# schema_electrica_statie_monitorizare.net
KiCad netlist of a schematic drawn in EAGLE
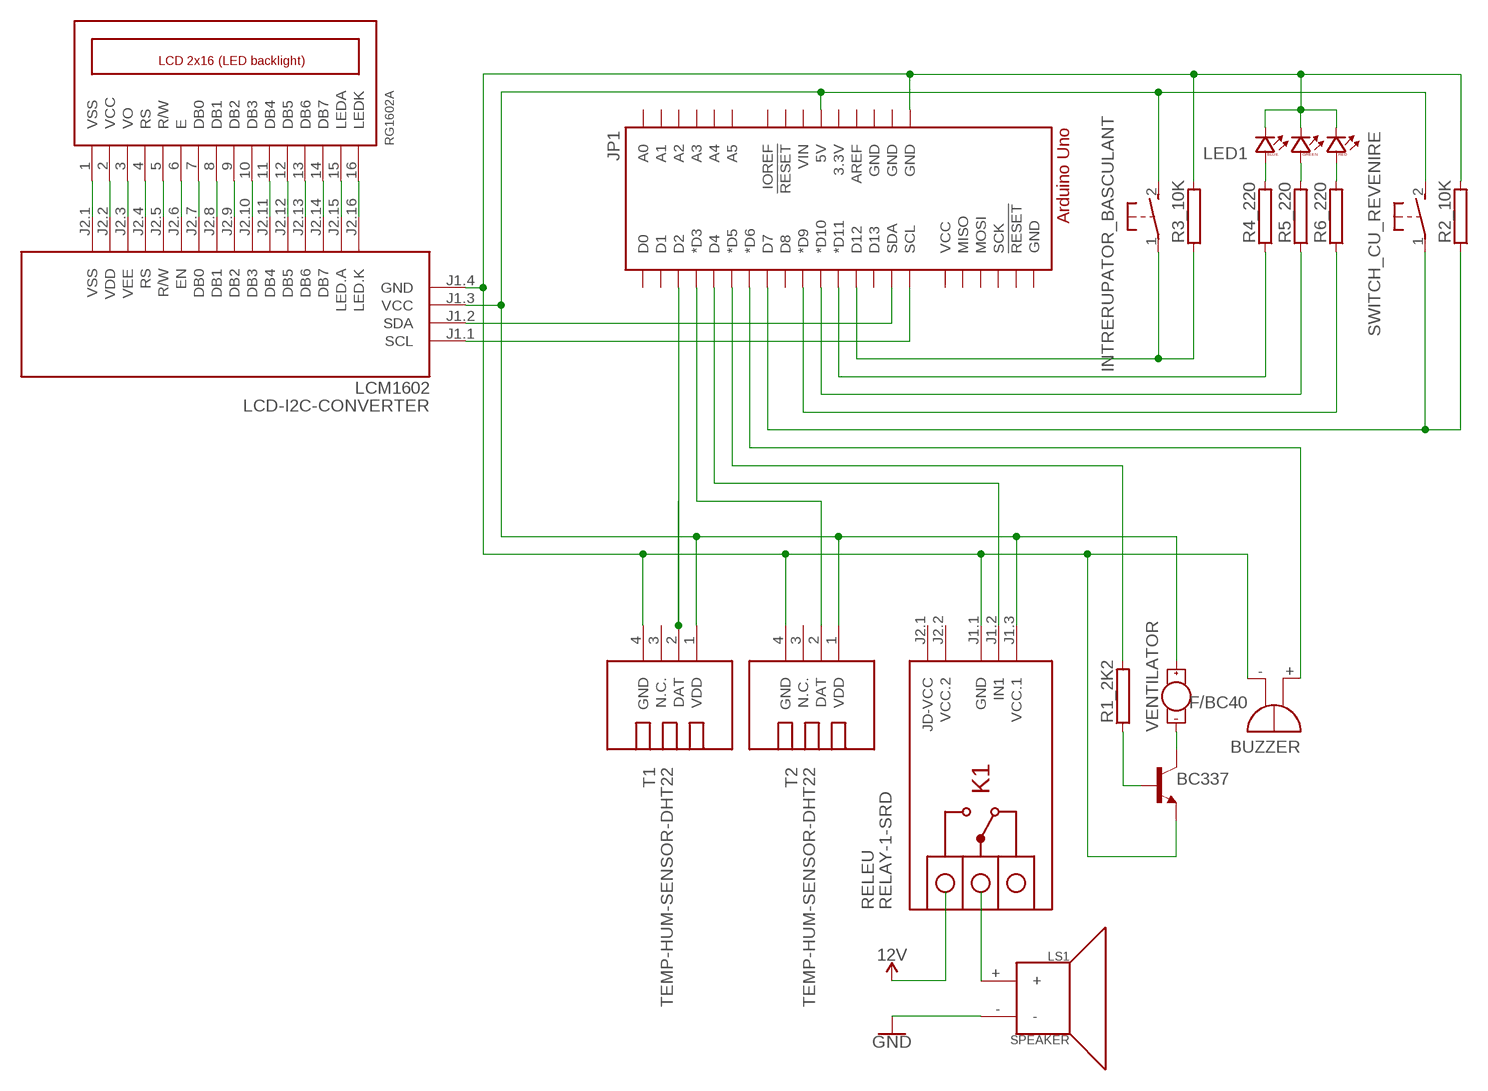
[diagram p0: schematic, sheet 1]

(export (version "E")
  (design (tool "Eeschema 10.0.6"))
  (components
    (comp (ref "BUZZER")
      (value "F/BC40")
      (footprint "eagle-import:F_BC40")
      (libsource (lib "eagle-import") (part "F/BC40"))
    )
    (comp (ref "INTRERUPATOR_BASCULANT")
      (value "31-XX")
      (footprint "eagle-import:B3F-31XX")
      (fields (field (name "MPN") "B3F-3100"))
      (libsource (lib "eagle-import") (part "31-XX"))
    )
    (comp (ref "JP1")
      (value "ARDUINO_R3")
      (footprint "eagle-import:ARDUINO_R3")
      (libsource (lib "eagle-import") (part "ARDUINO_R3"))
    )
    (comp (ref "LCM1602")
      (value "LCD-I2C-CONVERTER")
      (footprint "eagle-import:LCD-I2C-CONVERTER")
      (libsource (lib "eagle-import") (part "LCD-I2C-CONVERTER"))
    )
    (comp (ref "LED1")
      (value "F50360")
      (footprint "eagle-import:F50360")
      (libsource (lib "eagle-import") (part "F50360"))
    )
    (comp (ref "LS1")
      (value "SPEAKER")
      (footprint "eagle-import:PCB_MOUNT_SPEAKER")
      (libsource (lib "eagle-import") (part "SPEAKER"))
    )
    (comp (ref "R1_2K2")
      (value "RAC01")
      (footprint "eagle-import:AC01")
      (libsource (lib "eagle-import") (part "RAC01"))
    )
    (comp (ref "R2_10K")
      (value "RAC01")
      (footprint "eagle-import:AC01")
      (libsource (lib "eagle-import") (part "RAC01"))
    )
    (comp (ref "R3_10K")
      (value "RAC01")
      (footprint "eagle-import:AC01")
      (libsource (lib "eagle-import") (part "RAC01"))
    )
    (comp (ref "R4_220")
      (value "RAC01")
      (footprint "eagle-import:AC01")
      (libsource (lib "eagle-import") (part "RAC01"))
    )
    (comp (ref "R5_220")
      (value "RAC01")
      (footprint "eagle-import:AC01")
      (libsource (lib "eagle-import") (part "RAC01"))
    )
    (comp (ref "R6_220")
      (value "RAC01")
      (footprint "eagle-import:AC01")
      (libsource (lib "eagle-import") (part "RAC01"))
    )
    (comp (ref "RELEU")
      (value "RELAY-1-SRD")
      (footprint "eagle-import:RELAY-1-SRD")
      (libsource (lib "eagle-import") (part "RELAY-1-SRD"))
    )
    (comp (ref "RG1602A")
      (value "LCD_2X16_SIL")
      (footprint "eagle-import:HY-1602F")
      (libsource (lib "eagle-import") (part "LCD_2X16_SIL"))
    )
    (comp (ref "SWITCH_CU_REVENIRE")
      (value "31-XX")
      (footprint "eagle-import:B3F-31XX")
      (fields (field (name "MPN") "B3F-3100"))
      (libsource (lib "eagle-import") (part "31-XX"))
    )
    (comp (ref "T1")
      (value "TEMP-HUM-SENSOR-DHT22")
      (footprint "eagle-import:TEMP-HUM-SENSOR-DHT22")
      (libsource (lib "eagle-import") (part "TEMP-HUM-SENSOR-DHT22"))
    )
    (comp (ref "T2")
      (value "TEMP-HUM-SENSOR-DHT22")
      (footprint "eagle-import:TEMP-HUM-SENSOR-DHT22")
      (libsource (lib "eagle-import") (part "TEMP-HUM-SENSOR-DHT22"))
    )
    (comp (ref "T3")
      (value "BC337")
      (footprint "eagle-import:TO92")
      (libsource (lib "eagle-import") (part "BC337"))
    )
    (comp (ref "VENTILATOR")
      (value "MOTOR10MM")
      (footprint "eagle-import:VIBE-MOTOR-10MM")
      (libsource (lib "eagle-import") (part "MOTOR10MM"))
    )
  )
  (nets
    (net (code "1") (name "/VCC.2") (class "Default")
      (node (ref "RELEU") (pin "J2.2") (pinfunction "VCC.2_J2.2") (pintype "power_in"))
    )
    (net (code "3") (name "GND") (class "Default")
      (node (ref "LS1") (pin "-") (pinfunction "-_-") (pintype "bidirectional"))
    )
    (net (code "4") (name "Net-(INTRERUPATOR_BASCULANT-P)") (class "Default")
      (node (ref "INTRERUPATOR_BASCULANT") (pin "1") (pinfunction "P_1") (pintype "passive"))
      (node (ref "JP1") (pin "D12") (pinfunction "D12_D12") (pintype "bidirectional"))
      (node (ref "R3_10K") (pin "1") (pinfunction "1_1") (pintype "passive"))
    )
    (net (code "5") (name "Net-(INTRERUPATOR_BASCULANT-S)") (class "Default")
      (node (ref "INTRERUPATOR_BASCULANT") (pin "2") (pinfunction "S_2") (pintype "passive"))
      (node (ref "JP1") (pin "5V") (pinfunction "5V_5V") (pintype "bidirectional"))
      (node (ref "LCM1602") (pin "J1.3") (pinfunction "VCC_J1.3") (pintype "bidirectional"))
      (node (ref "RELEU") (pin "J1.3") (pinfunction "VCC.1_J1.3") (pintype "power_in"))
      (node (ref "SWITCH_CU_REVENIRE") (pin "2") (pinfunction "S_2") (pintype "passive"))
      (node (ref "T1") (pin "1") (pinfunction "VDD_1") (pintype "power_in"))
      (node (ref "T2") (pin "1") (pinfunction "VDD_1") (pintype "power_in"))
      (node (ref "VENTILATOR") (pin "+") (pinfunction "+_+") (pintype "bidirectional"))
    )
    (net (code "6") (name "Net-(JP1-*D3)") (class "Default")
      (node (ref "JP1") (pin "D3") (pinfunction "*D3_D3") (pintype "bidirectional"))
      (node (ref "T2") (pin "2") (pinfunction "DAT_2") (pintype "bidirectional"))
    )
    (net (code "7") (name "Net-(JP1-*D5)") (class "Default")
      (node (ref "JP1") (pin "D5") (pinfunction "*D5_D5") (pintype "bidirectional"))
      (node (ref "R1_2K2") (pin "2") (pinfunction "2_2") (pintype "passive"))
    )
    (net (code "8") (name "Net-(JP1-*D6)") (class "Default")
      (node (ref "BUZZER") (pin "+") (pinfunction "+_+") (pintype "passive"))
      (node (ref "JP1") (pin "D6") (pinfunction "*D6_D6") (pintype "bidirectional"))
    )
    (net (code "9") (name "Net-(JP1-*D9)") (class "Default")
      (node (ref "JP1") (pin "D9") (pinfunction "*D9_D9") (pintype "bidirectional"))
      (node (ref "R6_220") (pin "1") (pinfunction "1_1") (pintype "passive"))
    )
    (net (code "10") (name "Net-(JP1-*D10)") (class "Default")
      (node (ref "JP1") (pin "D10") (pinfunction "*D10_D10") (pintype "bidirectional"))
      (node (ref "R5_220") (pin "1") (pinfunction "1_1") (pintype "passive"))
    )
    (net (code "11") (name "Net-(JP1-*D11)") (class "Default")
      (node (ref "JP1") (pin "D11") (pinfunction "*D11_D11") (pintype "bidirectional"))
      (node (ref "R4_220") (pin "1") (pinfunction "1_1") (pintype "passive"))
    )
    (net (code "12") (name "Net-(LCM1602-DB0)") (class "Default")
      (node (ref "LCM1602") (pin "J2.7") (pinfunction "DB0_J2.7") (pintype "bidirectional"))
      (node (ref "RG1602A") (pin "7") (pinfunction "DB0_7") (pintype "bidirectional"))
    )
    (net (code "13") (name "Net-(LCM1602-DB1)") (class "Default")
      (node (ref "LCM1602") (pin "J2.8") (pinfunction "DB1_J2.8") (pintype "bidirectional"))
      (node (ref "RG1602A") (pin "8") (pinfunction "DB1_8") (pintype "bidirectional"))
    )
    (net (code "14") (name "Net-(LCM1602-DB2)") (class "Default")
      (node (ref "LCM1602") (pin "J2.9") (pinfunction "DB2_J2.9") (pintype "bidirectional"))
      (node (ref "RG1602A") (pin "9") (pinfunction "DB2_9") (pintype "bidirectional"))
    )
    (net (code "15") (name "Net-(LCM1602-DB3)") (class "Default")
      (node (ref "LCM1602") (pin "J2.10") (pinfunction "DB3_J2.10") (pintype "bidirectional"))
      (node (ref "RG1602A") (pin "10") (pinfunction "DB3_10") (pintype "bidirectional"))
    )
    (net (code "16") (name "Net-(LCM1602-DB4)") (class "Default")
      (node (ref "LCM1602") (pin "J2.11") (pinfunction "DB4_J2.11") (pintype "bidirectional"))
      (node (ref "RG1602A") (pin "11") (pinfunction "DB4_11") (pintype "bidirectional"))
    )
    (net (code "17") (name "Net-(LCM1602-DB5)") (class "Default")
      (node (ref "LCM1602") (pin "J2.12") (pinfunction "DB5_J2.12") (pintype "bidirectional"))
      (node (ref "RG1602A") (pin "12") (pinfunction "DB5_12") (pintype "bidirectional"))
    )
    (net (code "18") (name "Net-(LCM1602-DB6)") (class "Default")
      (node (ref "LCM1602") (pin "J2.13") (pinfunction "DB6_J2.13") (pintype "bidirectional"))
      (node (ref "RG1602A") (pin "13") (pinfunction "DB6_13") (pintype "bidirectional"))
    )
    (net (code "19") (name "Net-(LCM1602-DB7)") (class "Default")
      (node (ref "LCM1602") (pin "J2.14") (pinfunction "DB7_J2.14") (pintype "bidirectional"))
      (node (ref "RG1602A") (pin "14") (pinfunction "DB7_14") (pintype "bidirectional"))
    )
    (net (code "20") (name "Net-(LCM1602-EN)") (class "Default")
      (node (ref "LCM1602") (pin "J2.6") (pinfunction "EN_J2.6") (pintype "bidirectional"))
      (node (ref "RG1602A") (pin "6") (pinfunction "E_6") (pintype "input"))
    )
    (net (code "21") (name "Net-(LCM1602-GND)") (class "Default")
      (node (ref "BUZZER") (pin "-") (pinfunction "-_-") (pintype "passive"))
      (node (ref "JP1") (pin "GND@2") (pinfunction "GND_GND@2") (pintype "bidirectional"))
      (node (ref "LCM1602") (pin "J1.4") (pinfunction "GND_J1.4") (pintype "power_in"))
      (node (ref "LED1") (pin "BC") (pinfunction "BC_BC") (pintype "passive"))
      (node (ref "LED1") (pin "GC") (pinfunction "GC_GC") (pintype "passive"))
      (node (ref "LED1") (pin "RC") (pinfunction "RC_RC") (pintype "passive"))
      (node (ref "R2_10K") (pin "2") (pinfunction "2_2") (pintype "passive"))
      (node (ref "R3_10K") (pin "2") (pinfunction "2_2") (pintype "passive"))
      (node (ref "RELEU") (pin "J1.1") (pinfunction "GND_J1.1") (pintype "power_in"))
      (node (ref "T1") (pin "4") (pinfunction "GND_4") (pintype "power_in"))
      (node (ref "T2") (pin "4") (pinfunction "GND_4") (pintype "power_in"))
      (node (ref "T3") (pin "1") (pinfunction "E_1") (pintype "passive"))
    )
    (net (code "22") (name "Net-(LCM1602-LED.A)") (class "Default")
      (node (ref "LCM1602") (pin "J2.15") (pinfunction "LED.A_J2.15") (pintype "bidirectional"))
      (node (ref "RG1602A") (pin "15") (pinfunction "LEDA_15") (pintype "passive"))
    )
    (net (code "23") (name "Net-(LCM1602-LED.K)") (class "Default")
      (node (ref "LCM1602") (pin "J2.16") (pinfunction "LED.K_J2.16") (pintype "bidirectional"))
      (node (ref "RG1602A") (pin "16") (pinfunction "LEDK_16") (pintype "passive"))
    )
    (net (code "24") (name "Net-(LCM1602-RS)") (class "Default")
      (node (ref "LCM1602") (pin "J2.4") (pinfunction "RS_J2.4") (pintype "bidirectional"))
      (node (ref "RG1602A") (pin "4") (pinfunction "RS_4") (pintype "input"))
    )
    (net (code "25") (name "Net-(LCM1602-R{slash}W)") (class "Default")
      (node (ref "LCM1602") (pin "J2.5") (pinfunction "R/W_J2.5") (pintype "bidirectional"))
      (node (ref "RG1602A") (pin "5") (pinfunction "R/W_5") (pintype "input"))
    )
    (net (code "26") (name "Net-(LCM1602-SCL)") (class "Default")
      (node (ref "JP1") (pin "SCL") (pinfunction "SCL_SCL") (pintype "bidirectional"))
      (node (ref "LCM1602") (pin "J1.1") (pinfunction "SCL_J1.1") (pintype "power_in"))
    )
    (net (code "27") (name "Net-(LCM1602-SDA)") (class "Default")
      (node (ref "JP1") (pin "SDA") (pinfunction "SDA_SDA") (pintype "bidirectional"))
      (node (ref "LCM1602") (pin "J1.2") (pinfunction "SDA_J1.2") (pintype "bidirectional"))
    )
    (net (code "28") (name "Net-(LCM1602-VDD)") (class "Default")
      (node (ref "LCM1602") (pin "J2.2") (pinfunction "VDD_J2.2") (pintype "bidirectional"))
      (node (ref "RG1602A") (pin "2") (pinfunction "VCC_2") (pintype "power_in"))
    )
    (net (code "29") (name "Net-(LCM1602-VEE)") (class "Default")
      (node (ref "LCM1602") (pin "J2.3") (pinfunction "VEE_J2.3") (pintype "bidirectional"))
      (node (ref "RG1602A") (pin "3") (pinfunction "VO_3") (pintype "input"))
    )
    (net (code "30") (name "Net-(LCM1602-VSS)") (class "Default")
      (node (ref "LCM1602") (pin "J2.1") (pinfunction "VSS_J2.1") (pintype "bidirectional"))
      (node (ref "RG1602A") (pin "1") (pinfunction "VSS_1") (pintype "power_in"))
    )
    (net (code "31") (name "Net-(LED1-PadBA)") (class "Default")
      (node (ref "LED1") (pin "BA") (pinfunction "BA_BA") (pintype "passive"))
      (node (ref "R4_220") (pin "2") (pinfunction "2_2") (pintype "passive"))
    )
    (net (code "32") (name "Net-(LED1-PadGA)") (class "Default")
      (node (ref "LED1") (pin "GA") (pinfunction "GA_GA") (pintype "passive"))
      (node (ref "R5_220") (pin "2") (pinfunction "2_2") (pintype "passive"))
    )
    (net (code "33") (name "Net-(LED1-PadRA)") (class "Default")
      (node (ref "LED1") (pin "RA") (pinfunction "RA_RA") (pintype "passive"))
      (node (ref "R6_220") (pin "2") (pinfunction "2_2") (pintype "passive"))
    )
    (net (code "34") (name "Net-(RELEU-IN1)") (class "Default")
      (node (ref "JP1") (pin "D4") (pinfunction "D4_D4") (pintype "bidirectional"))
      (node (ref "RELEU") (pin "J1.2") (pinfunction "IN1_J1.2") (pintype "bidirectional"))
    )
    (net (code "35") (name "Net-(SWITCH_CU_REVENIRE-P)") (class "Default")
      (node (ref "JP1") (pin "D7") (pinfunction "D7_D7") (pintype "bidirectional"))
      (node (ref "R2_10K") (pin "1") (pinfunction "1_1") (pintype "passive"))
      (node (ref "SWITCH_CU_REVENIRE") (pin "1") (pinfunction "P_1") (pintype "passive"))
    )
    (net (code "36") (name "Net-(T1-DAT)") (class "Default")
      (node (ref "JP1") (pin "D2") (pinfunction "D2_D2") (pintype "bidirectional"))
      (node (ref "T1") (pin "2") (pinfunction "DAT_2") (pintype "bidirectional"))
    )
    (net (code "37") (name "Net-(T3-B)") (class "Default")
      (node (ref "R1_2K2") (pin "1") (pinfunction "1_1") (pintype "passive"))
      (node (ref "T3") (pin "2") (pinfunction "B_2") (pintype "passive"))
    )
    (net (code "38") (name "Net-(T3-C)") (class "Default")
      (node (ref "T3") (pin "3") (pinfunction "C_3") (pintype "passive"))
      (node (ref "VENTILATOR") (pin "-") (pinfunction "-_-") (pintype "bidirectional"))
    )
    (net (code "39") (name "unconnected-(JP1-GND-PadGND@1)") (class "Default")
      (node (ref "JP1") (pin "GND@1") (pinfunction "GND_GND@1") (pintype "bidirectional"))
    )
    (net (code "40") (name "unconnected-(JP1-GND-PadGND@3)") (class "Default")
      (node (ref "JP1") (pin "GND@3") (pinfunction "GND_GND@3") (pintype "bidirectional"))
    )
    (net (code "41") (name "unconnected-(JP1-GND-PadGND@4)") (class "Default")
      (node (ref "JP1") (pin "GND@4") (pinfunction "GND_GND@4") (pintype "bidirectional"))
    )
    (net (code "42") (name "unconnected-(JP1-Pad3.3V)") (class "Default")
      (node (ref "JP1") (pin "3.3V") (pinfunction "3.3V_3.3V") (pintype "bidirectional"))
    )
    (net (code "43") (name "unconnected-(JP1-PadA0)") (class "Default")
      (node (ref "JP1") (pin "A0") (pinfunction "A0_A0") (pintype "bidirectional"))
    )
    (net (code "44") (name "unconnected-(JP1-PadA1)") (class "Default")
      (node (ref "JP1") (pin "A1") (pinfunction "A1_A1") (pintype "bidirectional"))
    )
    (net (code "45") (name "unconnected-(JP1-PadA2)") (class "Default")
      (node (ref "JP1") (pin "A2") (pinfunction "A2_A2") (pintype "bidirectional"))
    )
    (net (code "46") (name "unconnected-(JP1-PadA3)") (class "Default")
      (node (ref "JP1") (pin "A3") (pinfunction "A3_A3") (pintype "bidirectional"))
    )
    (net (code "47") (name "unconnected-(JP1-PadA4)") (class "Default")
      (node (ref "JP1") (pin "A4") (pinfunction "A4_A4") (pintype "bidirectional"))
    )
    (net (code "48") (name "unconnected-(JP1-PadA5)") (class "Default")
      (node (ref "JP1") (pin "A5") (pinfunction "A5_A5") (pintype "bidirectional"))
    )
    (net (code "49") (name "unconnected-(JP1-PadAREF)") (class "Default")
      (node (ref "JP1") (pin "AREF") (pinfunction "AREF_AREF") (pintype "bidirectional"))
    )
    (net (code "50") (name "unconnected-(JP1-PadD0)") (class "Default")
      (node (ref "JP1") (pin "D0") (pinfunction "D0_D0") (pintype "bidirectional"))
    )
    (net (code "51") (name "unconnected-(JP1-PadD1)") (class "Default")
      (node (ref "JP1") (pin "D1") (pinfunction "D1_D1") (pintype "bidirectional"))
    )
    (net (code "52") (name "unconnected-(JP1-PadD8)") (class "Default")
      (node (ref "JP1") (pin "D8") (pinfunction "D8_D8") (pintype "bidirectional"))
    )
    (net (code "53") (name "unconnected-(JP1-PadD13)") (class "Default")
      (node (ref "JP1") (pin "D13") (pinfunction "D13_D13") (pintype "bidirectional"))
    )
    (net (code "54") (name "unconnected-(JP1-PadIOREF)") (class "Default")
      (node (ref "JP1") (pin "IOREF") (pinfunction "IOREF_IOREF") (pintype "bidirectional"))
    )
    (net (code "55") (name "unconnected-(JP1-PadMISO)") (class "Default")
      (node (ref "JP1") (pin "MISO") (pinfunction "MISO_MISO") (pintype "bidirectional"))
    )
    (net (code "56") (name "unconnected-(JP1-PadMOSI)") (class "Default")
      (node (ref "JP1") (pin "MOSI") (pinfunction "MOSI_MOSI") (pintype "bidirectional"))
    )
    (net (code "57") (name "unconnected-(JP1-PadSCK)") (class "Default")
      (node (ref "JP1") (pin "SCK") (pinfunction "SCK_SCK") (pintype "bidirectional"))
    )
    (net (code "58") (name "unconnected-(JP1-PadVCC)") (class "Default")
      (node (ref "JP1") (pin "VCC") (pinfunction "VCC_VCC") (pintype "bidirectional"))
    )
    (net (code "59") (name "unconnected-(JP1-PadVIN)") (class "Default")
      (node (ref "JP1") (pin "VIN") (pinfunction "VIN_VIN") (pintype "bidirectional"))
    )
    (net (code "60") (name "unconnected-(JP1-~{RESET}-PadRESET@1)") (class "Default")
      (node (ref "JP1") (pin "RESET@1") (pinfunction "~{RESET}_RESET@1") (pintype "bidirectional"))
    )
    (net (code "61") (name "unconnected-(JP1-~{RESET}-PadRESET@2)") (class "Default")
      (node (ref "JP1") (pin "RESET@2") (pinfunction "~{RESET}_RESET@2") (pintype "bidirectional"))
    )
    (net (code "62") (name "unconnected-(LS1-Pad+)") (class "Default")
      (node (ref "LS1") (pin "+") (pinfunction "+_+") (pintype "bidirectional"))
    )
    (net (code "63") (name "unconnected-(RELEU-JD-VCC-PadJ2.1)") (class "Default")
      (node (ref "RELEU") (pin "J2.1") (pinfunction "JD-VCC_J2.1") (pintype "bidirectional"))
    )
    (net (code "64") (name "unconnected-(T1-N.C.-Pad3)") (class "Default")
      (node (ref "T1") (pin "3") (pinfunction "N.C._3") (pintype "passive"))
    )
    (net (code "65") (name "unconnected-(T2-N.C.-Pad3)") (class "Default")
      (node (ref "T2") (pin "3") (pinfunction "N.C._3") (pintype "passive"))
    )
  )
)
